# IPMI.net
KiCad netlist of a schematic drawn in Altium Designer
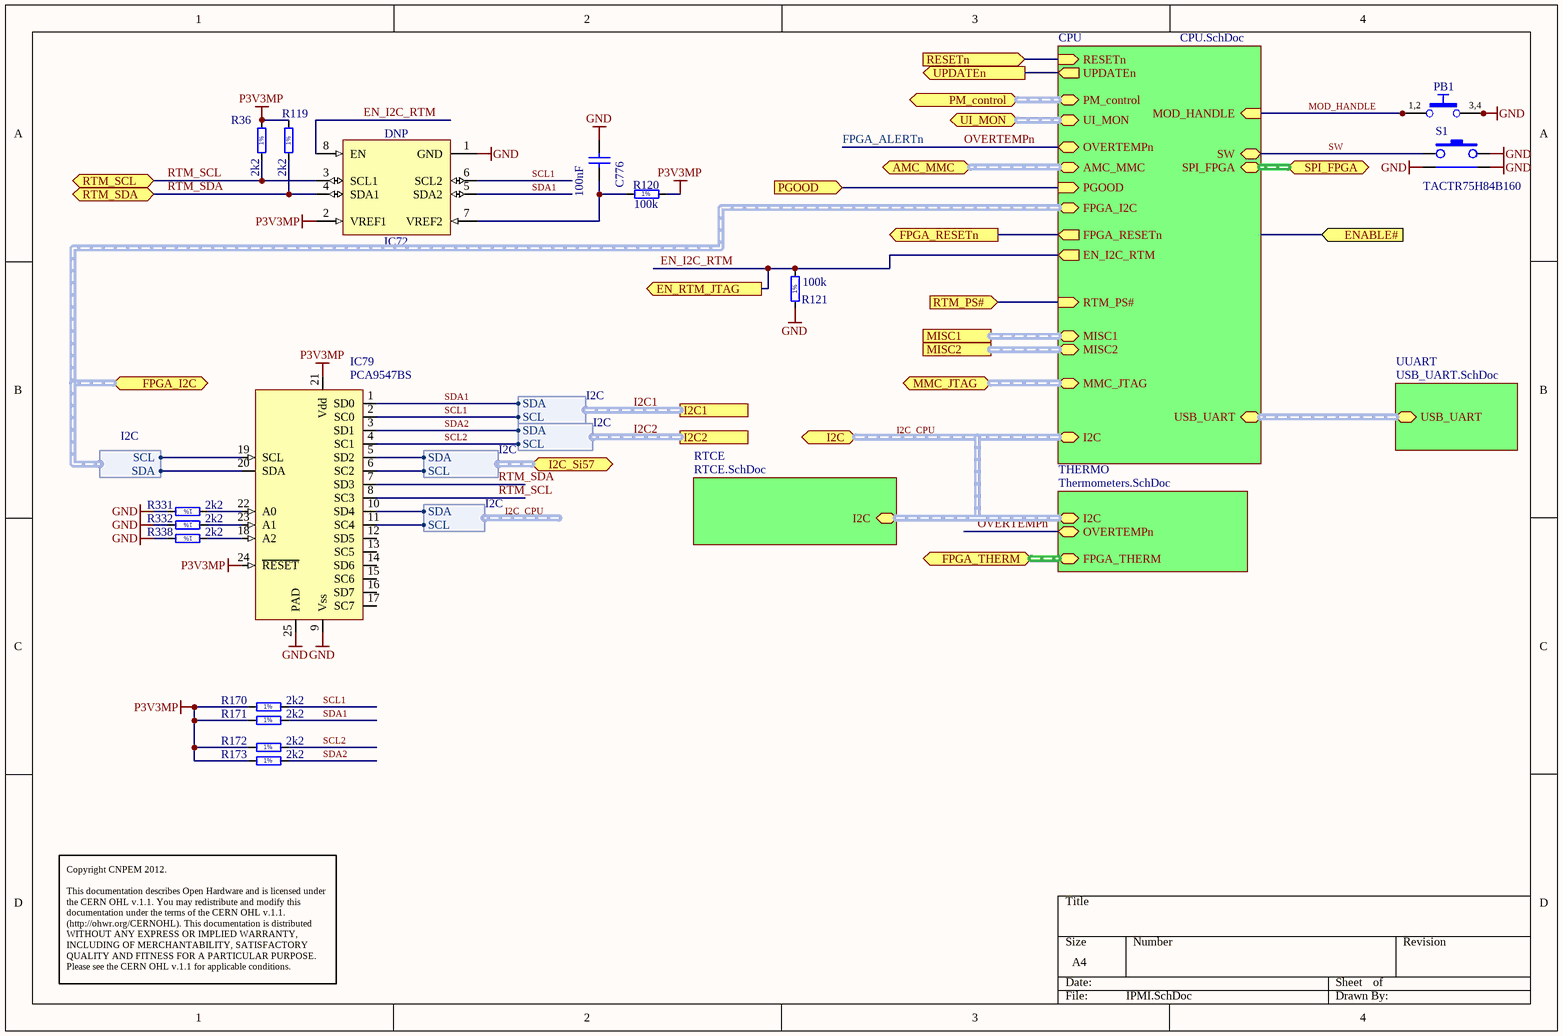
[diagram p0: IPMI.SchDoc]

(export (version "E")
  (design (tool "Eeschema 10.0.6"))
  (components
    (comp (ref "C776")
      (value "100nF")
      (footprint "CAPC0603X33N")
      (description "Non-polarised capacitor")
      (fields
        (field (name "PART NUMBER") "CC0201_100NF_6.3V_10%_X5R")
        (field (name "VOLTAGE") "6.3V")
        (field (name "AUTHOR") "CERN DEM JLC")
      )
      (libsource (lib "Capacitors") (part "Capacitor - non polarized"))
    )
    (comp (ref "IC72")
      (value "DNP")
      (footprint "SOP65P400X130-8N")
      (description "Dual Bidirectional I2C Bus And SMBus Voltage-Level Translator")
      (fields
        (field (name "PART NUMBER") "PCA9306DCTR")
        (field (name "MANUFACTURER") "TEXAS INSTRUMENTS")
        (field (name "AUTHOR") "CERN DEM JLC")
      )
      (libsource (lib "ICs And Semiconductors") (part "PCA9306DC"))
    )
    (comp (ref "IC79")
      (value "PCA9547BS")
      (footprint "HVQFN24")
      (description "8-channel I2C-bus multiplexer with reset")
      (libsource (lib "LIBRARY_SCH") (part "IIC_MUX_PCA9547"))
    )
    (comp (ref "PB1")
      (value "Push Button")
      (footprint "SW_C&K_HDT0001")
      (description "Push-Button Switch SPDT")
      (fields
        (field (name "PART NUMBER") "SW_C&K_HDT0001")
        (field (name "MANUFACTURER") "C&K")
        (field (name "AUTHOR") "CERN DEM JLC")
      )
      (libsource (lib "Eletro-mechanical") (part "PB SPST 12NO-34NO"))
    )
    (comp (ref "R36")
      (value "2k2")
      (footprint "RESC1005X40N")
      (description "Resistor - 1%")
      (fields
        (field (name "PART NUMBER") "R0402_2K2_1%_0.0625W_100PPM")
        (field (name "POWER") "0.0625W")
        (field (name "AUTHOR") "CERN DEM JLC")
      )
      (libsource (lib "Resistors") (part "Resistor - 1%"))
    )
    (comp (ref "R119")
      (value "2k2")
      (footprint "RESC1005X40N")
      (description "Resistor - 1%")
      (fields
        (field (name "PART NUMBER") "R0402_2K2_1%_0.0625W_100PPM")
        (field (name "POWER") "0.0625W")
        (field (name "AUTHOR") "CERN DEM JLC")
      )
      (libsource (lib "Resistors") (part "Resistor - 1%"))
    )
    (comp (ref "R120")
      (value "100k")
      (footprint "RESC1005X40N")
      (description "Resistor - 1%")
      (fields
        (field (name "PART NUMBER") "R0402_100K_1%_0.0625W_100PPM")
        (field (name "POWER") "0.0625W")
        (field (name "AUTHOR") "CERN DEM JLC")
      )
      (libsource (lib "Resistors") (part "Resistor - 1%"))
    )
    (comp (ref "R121")
      (value "100k")
      (footprint "RESC1005X40N")
      (description "Resistor - 1%")
      (fields
        (field (name "PART NUMBER") "R0402_100K_1%_0.0625W_100PPM")
        (field (name "POWER") "0.0625W")
        (field (name "AUTHOR") "CERN DEM JLC")
      )
      (libsource (lib "Resistors") (part "Resistor - 1%"))
    )
    (comp (ref "R170")
      (value "2k2")
      (footprint "RESC1005X40N")
      (description "Resistor - 1%")
      (fields
        (field (name "PART NUMBER") "R0402_2K2_1%_0.0625W_100PPM")
        (field (name "POWER") "0.0625W")
        (field (name "AUTHOR") "CERN DEM JLC")
      )
      (libsource (lib "Resistors") (part "Resistor - 1%"))
    )
    (comp (ref "R171")
      (value "2k2")
      (footprint "RESC1005X40N")
      (description "Resistor - 1%")
      (fields
        (field (name "PART NUMBER") "R0402_2K2_1%_0.0625W_100PPM")
        (field (name "POWER") "0.0625W")
        (field (name "AUTHOR") "CERN DEM JLC")
      )
      (libsource (lib "Resistors") (part "Resistor - 1%"))
    )
    (comp (ref "R172")
      (value "2k2")
      (footprint "RESC1005X40N")
      (description "Resistor - 1%")
      (fields
        (field (name "PART NUMBER") "R0402_2K2_1%_0.0625W_100PPM")
        (field (name "POWER") "0.0625W")
        (field (name "AUTHOR") "CERN DEM JLC")
      )
      (libsource (lib "Resistors") (part "Resistor - 1%"))
    )
    (comp (ref "R173")
      (value "2k2")
      (footprint "RESC1005X40N")
      (description "Resistor - 1%")
      (fields
        (field (name "PART NUMBER") "R0402_2K2_1%_0.0625W_100PPM")
        (field (name "POWER") "0.0625W")
        (field (name "AUTHOR") "CERN DEM JLC")
      )
      (libsource (lib "Resistors") (part "Resistor - 1%"))
    )
    (comp (ref "R331")
      (value "2k2")
      (footprint "RESC1005X40N")
      (description "Resistor - 1%")
      (fields
        (field (name "PART NUMBER") "R0402_2K2_1%_0.0625W_100PPM")
        (field (name "POWER") "0.0625W")
        (field (name "AUTHOR") "CERN DEM JLC")
      )
      (libsource (lib "Resistors") (part "Resistor - 1%"))
    )
    (comp (ref "R332")
      (value "2k2")
      (footprint "RESC1005X40N")
      (description "Resistor - 1%")
      (fields
        (field (name "PART NUMBER") "R0402_2K2_1%_0.0625W_100PPM")
        (field (name "POWER") "0.0625W")
        (field (name "AUTHOR") "CERN DEM JLC")
      )
      (libsource (lib "Resistors") (part "Resistor - 1%"))
    )
    (comp (ref "R338")
      (value "2k2")
      (footprint "RESC1005X40N")
      (description "Resistor - 1%")
      (fields
        (field (name "PART NUMBER") "R0402_2K2_1%_0.0625W_100PPM")
        (field (name "POWER") "0.0625W")
        (field (name "AUTHOR") "CERN DEM JLC")
      )
      (libsource (lib "Resistors") (part "Resistor - 1%"))
    )
    (comp (ref "S1")
      (value "TACTR75H84B160")
      (footprint "PB_ALPS_SKHHLQA010")
      (description "Push button")
      (libsource (lib "LIBRARY_SCH") (part "SW-PB_RA_5.8mm"))
    )
  )
  (nets
    (net (code "14") (name "/EN_I2C_RTM") (class "Default")
      (node (ref "IC72") (pin "8") (pinfunction "EN_8") (pintype "input"))
      (node (ref "R121") (pin "2") (pinfunction "2_2") (pintype "passive"))
    )
    (net (code "24") (name "/MOD_HANDLE") (class "Default")
      (node (ref "PB1") (pin "1") (pinfunction "1_1") (pintype "passive"))
      (node (ref "PB1") (pin "2") (pinfunction "2_2") (pintype "passive"))
    )
    (net (code "29") (name "/RTM_SCL") (class "Default")
      (node (ref "IC72") (pin "3") (pinfunction "SCL1_3") (pintype "bidirectional"))
      (node (ref "IC79") (pin "8") (pinfunction "SC3_8") (pintype "bidirectional"))
      (node (ref "R36") (pin "1") (pinfunction "1_1") (pintype "passive"))
    )
    (net (code "30") (name "/RTM_SDA") (class "Default")
      (node (ref "IC72") (pin "4") (pinfunction "SDA1_4") (pintype "bidirectional"))
      (node (ref "IC79") (pin "7") (pinfunction "SD3_7") (pintype "bidirectional"))
      (node (ref "R119") (pin "1") (pinfunction "1_1") (pintype "passive"))
    )
    (net (code "31") (name "/SCL1") (class "Default")
      (node (ref "IC72") (pin "6") (pinfunction "SCL2_6") (pintype "bidirectional"))
      (node (ref "IC79") (pin "2") (pinfunction "SC0_2") (pintype "bidirectional"))
      (node (ref "R170") (pin "2") (pinfunction "2_2") (pintype "passive"))
    )
    (net (code "32") (name "/SCL2") (class "Default")
      (node (ref "IC79") (pin "4") (pinfunction "SC1_4") (pintype "bidirectional"))
      (node (ref "R172") (pin "2") (pinfunction "2_2") (pintype "passive"))
    )
    (net (code "33") (name "/SDA1") (class "Default")
      (node (ref "IC72") (pin "5") (pinfunction "SDA2_5") (pintype "bidirectional"))
      (node (ref "IC79") (pin "1") (pinfunction "SD0_1") (pintype "bidirectional"))
      (node (ref "R171") (pin "2") (pinfunction "2_2") (pintype "passive"))
    )
    (net (code "34") (name "/SDA2") (class "Default")
      (node (ref "IC79") (pin "3") (pinfunction "SD1_3") (pintype "bidirectional"))
      (node (ref "R173") (pin "2") (pinfunction "2_2") (pintype "passive"))
    )
    (net (code "36") (name "/SW") (class "Default")
      (node (ref "S1") (pin "1") (pinfunction "1_1") (pintype "passive"))
    )
    (net (code "42") (name "GND") (class "Default")
      (node (ref "C776") (pin "2") (pinfunction "2_2") (pintype "passive"))
      (node (ref "IC72") (pin "1") (pinfunction "GND_1") (pintype "power_in"))
      (node (ref "IC79") (pin "25") (pinfunction "PAD_25") (pintype "power_in"))
      (node (ref "IC79") (pin "9") (pinfunction "Vss_9") (pintype "power_in"))
      (node (ref "PB1") (pin "3") (pinfunction "3_3") (pintype "passive"))
      (node (ref "PB1") (pin "4") (pinfunction "4_4") (pintype "passive"))
      (node (ref "R121") (pin "1") (pinfunction "1_1") (pintype "passive"))
      (node (ref "R331") (pin "2") (pinfunction "2_2") (pintype "passive"))
      (node (ref "R332") (pin "2") (pinfunction "2_2") (pintype "passive"))
      (node (ref "R338") (pin "2") (pinfunction "2_2") (pintype "passive"))
      (node (ref "S1") (pin "2") (pinfunction "2_2") (pintype "passive"))
      (node (ref "S1") (pin "3") (pinfunction "3_3") (pintype "passive"))
      (node (ref "S1") (pin "4") (pinfunction "4_4") (pintype "passive"))
    )
    (net (code "43") (name "Net-(IC72-VREF2)") (class "Default")
      (node (ref "C776") (pin "1") (pinfunction "1_1") (pintype "passive"))
      (node (ref "IC72") (pin "7") (pinfunction "VREF2_7") (pintype "input"))
      (node (ref "R120") (pin "1") (pinfunction "1_1") (pintype "passive"))
    )
    (net (code "44") (name "Net-(IC79-A0)") (class "Default")
      (node (ref "IC79") (pin "22") (pinfunction "A0_22") (pintype "input"))
      (node (ref "R331") (pin "1") (pinfunction "1_1") (pintype "passive"))
    )
    (net (code "45") (name "Net-(IC79-A1)") (class "Default")
      (node (ref "IC79") (pin "23") (pinfunction "A1_23") (pintype "input"))
      (node (ref "R332") (pin "1") (pinfunction "1_1") (pintype "passive"))
    )
    (net (code "46") (name "Net-(IC79-A2)") (class "Default")
      (node (ref "IC79") (pin "18") (pinfunction "A2_18") (pintype "input"))
      (node (ref "R338") (pin "1") (pinfunction "1_1") (pintype "passive"))
    )
    (net (code "47") (name "P3V3MP") (class "Default")
      (node (ref "IC72") (pin "2") (pinfunction "VREF1_2") (pintype "input"))
      (node (ref "IC79") (pin "21") (pinfunction "Vdd_21") (pintype "power_in"))
      (node (ref "IC79") (pin "24") (pinfunction "~{RESET}_24") (pintype "input"))
      (node (ref "R119") (pin "2") (pinfunction "2_2") (pintype "passive"))
      (node (ref "R120") (pin "2") (pinfunction "2_2") (pintype "passive"))
      (node (ref "R170") (pin "1") (pinfunction "1_1") (pintype "passive"))
      (node (ref "R171") (pin "1") (pinfunction "1_1") (pintype "passive"))
      (node (ref "R172") (pin "1") (pinfunction "1_1") (pintype "passive"))
      (node (ref "R173") (pin "1") (pinfunction "1_1") (pintype "passive"))
      (node (ref "R36") (pin "2") (pinfunction "2_2") (pintype "passive"))
    )
    (net (code "48") (name "unconnected-(IC79-SC2-Pad6)") (class "Default")
      (node (ref "IC79") (pin "6") (pinfunction "SC2_6") (pintype "bidirectional"))
    )
    (net (code "49") (name "unconnected-(IC79-SC4-Pad11)") (class "Default")
      (node (ref "IC79") (pin "11") (pinfunction "SC4_11") (pintype "bidirectional"))
    )
    (net (code "50") (name "unconnected-(IC79-SC5-Pad13)") (class "Default")
      (node (ref "IC79") (pin "13") (pinfunction "SC5_13") (pintype "bidirectional"))
    )
    (net (code "51") (name "unconnected-(IC79-SC6-Pad15)") (class "Default")
      (node (ref "IC79") (pin "15") (pinfunction "SC6_15") (pintype "bidirectional"))
    )
    (net (code "52") (name "unconnected-(IC79-SC7-Pad17)") (class "Default")
      (node (ref "IC79") (pin "17") (pinfunction "SC7_17") (pintype "bidirectional"))
    )
    (net (code "53") (name "unconnected-(IC79-SCL-Pad19)") (class "Default")
      (node (ref "IC79") (pin "19") (pinfunction "SCL_19") (pintype "input"))
    )
    (net (code "54") (name "unconnected-(IC79-SD2-Pad5)") (class "Default")
      (node (ref "IC79") (pin "5") (pinfunction "SD2_5") (pintype "bidirectional"))
    )
    (net (code "55") (name "unconnected-(IC79-SD4-Pad10)") (class "Default")
      (node (ref "IC79") (pin "10") (pinfunction "SD4_10") (pintype "bidirectional"))
    )
    (net (code "56") (name "unconnected-(IC79-SD5-Pad12)") (class "Default")
      (node (ref "IC79") (pin "12") (pinfunction "SD5_12") (pintype "bidirectional"))
    )
    (net (code "57") (name "unconnected-(IC79-SD6-Pad14)") (class "Default")
      (node (ref "IC79") (pin "14") (pinfunction "SD6_14") (pintype "bidirectional"))
    )
    (net (code "58") (name "unconnected-(IC79-SD7-Pad16)") (class "Default")
      (node (ref "IC79") (pin "16") (pinfunction "SD7_16") (pintype "bidirectional"))
    )
    (net (code "59") (name "unconnected-(IC79-SDA-Pad20)") (class "Default")
      (node (ref "IC79") (pin "20") (pinfunction "SDA_20") (pintype "bidirectional"))
    )
  )
)
